# Simulation.net
KiCad netlist of a schematic drawn in Altium Designer
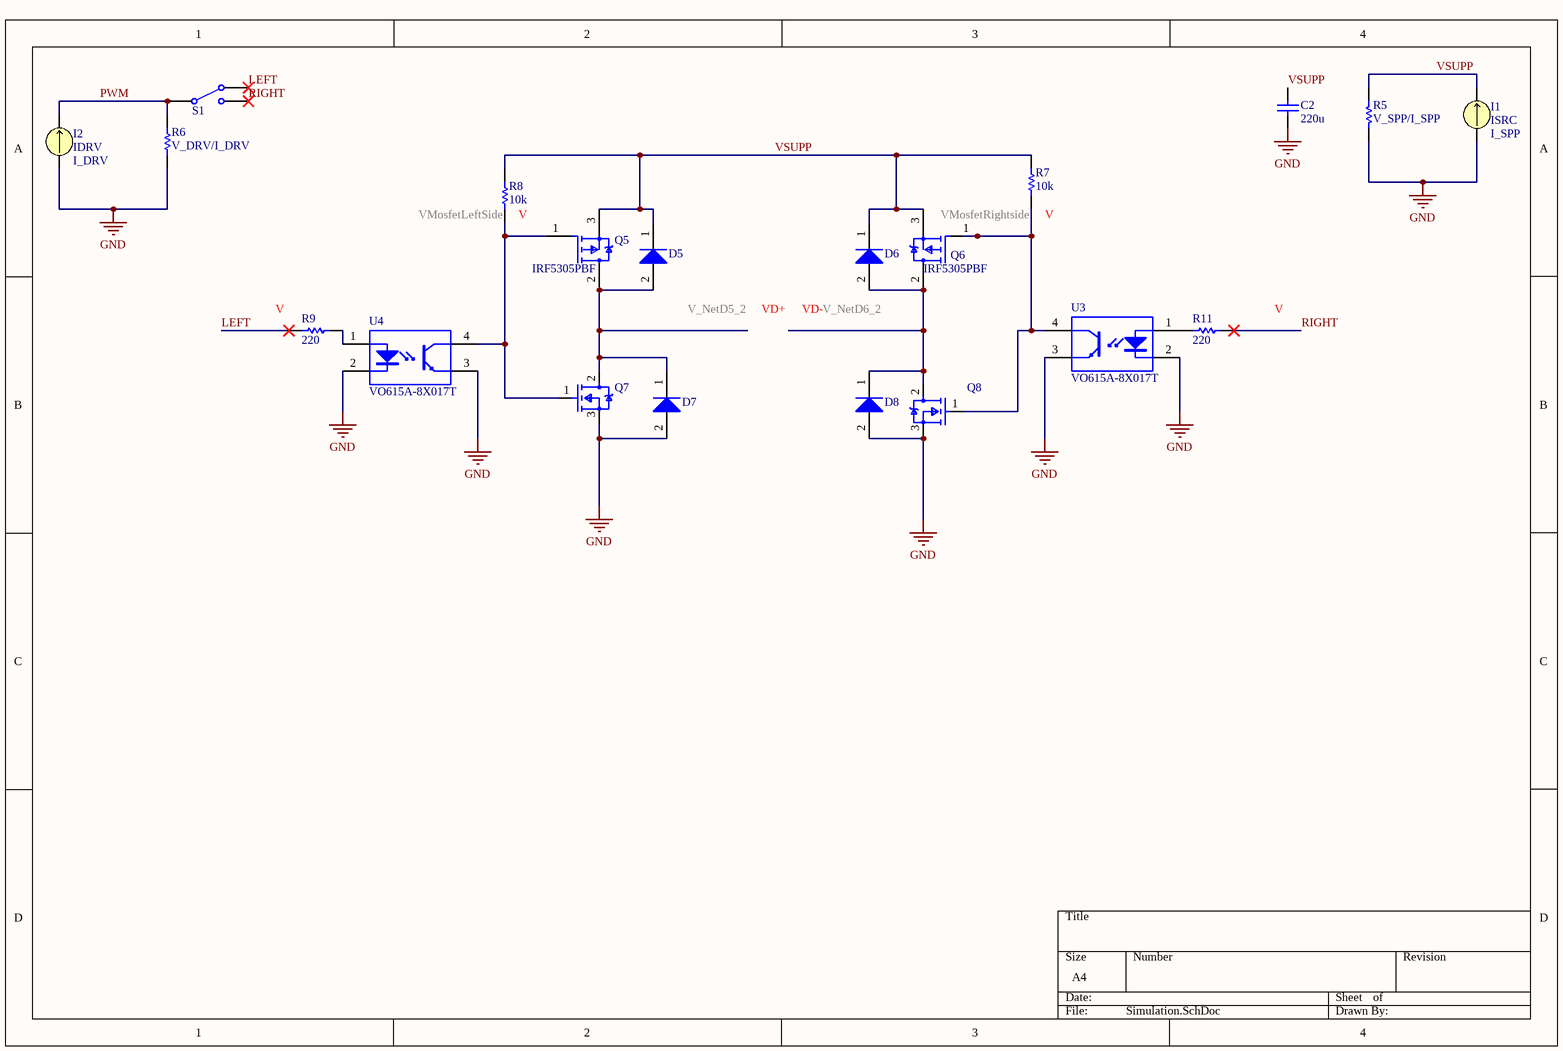
[diagram p0: Simulation.SchDoc]

(export (version "E")
  (design (tool "Eeschema 10.0.6"))
  (components
    (comp (ref "C2")
      (value "220u")
      (description "Capacitor")
      (libsource (lib "Simulation Generic Components") (part "Capacitor"))
    )
    (comp (ref "D5")
      (value "MUR410RLG")
      (footprint "ONSC-AXIAL_LEAD-2-267-05_V")
      (description "SWITCHMODE(TM) Power Rectifier, 2-Pin Axial_Lead, Pb-Free, Tape and Reel")
      (fields (field (name "MANUFACTURER") "On Semiconductor"))
      (libsource (lib "Altium Content Vault") (part "ONSC-D-K1A2-2"))
    )
    (comp (ref "D6")
      (value "MUR410RLG")
      (footprint "ONSC-AXIAL_LEAD-2-267-05_V")
      (description "SWITCHMODE(TM) Power Rectifier, 2-Pin Axial_Lead, Pb-Free, Tape and Reel")
      (fields (field (name "MANUFACTURER") "On Semiconductor"))
      (libsource (lib "Altium Content Vault") (part "ONSC-D-K1A2-2"))
    )
    (comp (ref "D7")
      (value "MUR410RLG")
      (footprint "ONSC-AXIAL_LEAD-2-267-05_V")
      (description "SWITCHMODE(TM) Power Rectifier, 2-Pin Axial_Lead, Pb-Free, Tape and Reel")
      (fields (field (name "MANUFACTURER") "On Semiconductor"))
      (libsource (lib "Altium Content Vault") (part "ONSC-D-K1A2-2"))
    )
    (comp (ref "D8")
      (value "MUR410RLG")
      (footprint "ONSC-AXIAL_LEAD-2-267-05_V")
      (description "SWITCHMODE(TM) Power Rectifier, 2-Pin Axial_Lead, Pb-Free, Tape and Reel")
      (fields (field (name "MANUFACTURER") "On Semiconductor"))
      (libsource (lib "Altium Content Vault") (part "ONSC-D-K1A2-2"))
    )
    (comp (ref "I1")
      (value "ISRC")
      (description "Current Source")
      (fields (field (name "ALTIUM_VALUE") "I_SPP") (field (name "PUBLISHER") "Altium Limited"))
      (libsource (lib "Simulation Generic Components") (part "ISRC"))
    )
    (comp (ref "I2")
      (value "IDRV")
      (description "Current Source")
      (fields (field (name "DC MAGNITUDE") "I_DRV") (field (name "PUBLISHER") "Altium Limited"))
      (libsource (lib "Simulation Generic Components") (part "ISRC"))
    )
    (comp (ref "Q5")
      (value "IRF5305PBF")
      (footprint "FP-PG-TO220-3-0")
      (description "MOSFET P-CH 55V 31A TO-220AB")
      (fields
        (field (name "OCTOPART") "https://octopart.com/irf5305pbf-infineon-65873396")
        (field (name "MANUFACTURER") "Infineon")
      )
      (libsource (lib "Altium Content Vault") (part "ef9d0aacdf366ab529cd174aea9d313"))
    )
    (comp (ref "Q6")
      (value "IRF5305PBF")
      (footprint "FP-PG-TO220-3-0")
      (description "MOSFET P-CH 55V 31A TO-220AB")
      (fields
        (field (name "OCTOPART") "https://octopart.com/irf5305pbf-infineon-65873396")
        (field (name "MANUFACTURER") "Infineon")
      )
      (libsource (lib "Altium Content Vault") (part "ef9d0aacdf366ab529cd174aea9d313"))
    )
    (comp (ref "Q7")
      (value "Trans_Infineon_IRF540NPBF_eec")
      (footprint "Infineon_IRF540NPBF_0")
      (description "TRANS MOSFET N-CH 100V 33A TO-220AB")
      (fields (field (name "PART NUMBER") "IRF540NPBF") (field (name "MANUFACTURER") "Infineon"))
      (libsource (lib "Trans_Infineon_IRF540NPBF_eec") (part "Trans_Infineon_IRF540NPBF_eec"))
    )
    (comp (ref "Q8")
      (value "Trans_Infineon_IRF540NPBF_eec")
      (footprint "Infineon_IRF540NPBF_0")
      (description "TRANS MOSFET N-CH 100V 33A TO-220AB")
      (fields (field (name "PART NUMBER") "IRF540NPBF") (field (name "MANUFACTURER") "Infineon"))
      (libsource (lib "Trans_Infineon_IRF540NPBF_eec") (part "Trans_Infineon_IRF540NPBF_eec"))
    )
    (comp (ref "R5")
      (value "V_SPP/I_SPP")
      (description "Resistor")
      (libsource (lib "Simulation Generic Components") (part "Resistor"))
    )
    (comp (ref "R6")
      (value "V_DRV/I_DRV")
      (description "Resistor")
      (libsource (lib "Simulation Generic Components") (part "Resistor"))
    )
    (comp (ref "R7")
      (value "10k")
      (description "Resistor")
      (libsource (lib "Simulation Generic Components") (part "Resistor"))
    )
    (comp (ref "R8")
      (value "10k")
      (description "Resistor")
      (libsource (lib "Simulation Generic Components") (part "Resistor"))
    )
    (comp (ref "R9")
      (value "220")
      (description "Resistor")
      (libsource (lib "Simulation Generic Components") (part "Resistor"))
    )
    (comp (ref "R11")
      (value "220")
      (description "Resistor")
      (libsource (lib "Simulation Generic Components") (part "Resistor"))
    )
    (comp (ref "S1")
      (value "Single-Pole, Double-Throw Switch")
      (libsource (lib "Simulation Generic Components") (part "SPDT SW"))
    )
    (comp (ref "U3")
      (value "VO615A-8X017T")
      (footprint "VISH-VO615A-XX017T_V")
      (fields (field (name "MANUFACTURER") "Vishay"))
      (libsource (lib "Altium Content Vault") (part "OPTO-AKEC-4"))
    )
    (comp (ref "U4")
      (value "VO615A-8X017T")
      (footprint "VISH-VO615A-XX017T_V")
      (fields (field (name "MANUFACTURER") "Vishay"))
      (libsource (lib "Altium Content Vault") (part "OPTO-AKEC-4"))
    )
  )
  (nets
    (net (code "2") (name "/LEFT") (class "Default")
      (node (ref "R9") (pin "2") (pinfunction "2_2") (pintype "passive"))
      (node (ref "S1") (pin "3") (pinfunction "3_3") (pintype "passive"))
    )
    (net (code "3") (name "/PWM") (class "Default")
      (node (ref "I2") (pin "2") (pinfunction "2_2") (pintype "passive"))
      (node (ref "R6") (pin "2") (pinfunction "2_2") (pintype "passive"))
      (node (ref "S1") (pin "1") (pinfunction "1_1") (pintype "passive"))
    )
    (net (code "4") (name "/RIGHT") (class "Default")
      (node (ref "R11") (pin "1") (pinfunction "1_1") (pintype "passive"))
      (node (ref "S1") (pin "2") (pinfunction "2_2") (pintype "passive"))
    )
    (net (code "5") (name "/VSUPP") (class "Default")
      (node (ref "C2") (pin "1") (pinfunction "1_1") (pintype "passive"))
      (node (ref "D5") (pin "1") (pinfunction "K_1") (pintype "passive"))
      (node (ref "D6") (pin "1") (pinfunction "K_1") (pintype "passive"))
      (node (ref "I1") (pin "2") (pinfunction "2_2") (pintype "passive"))
      (node (ref "Q5") (pin "3") (pinfunction "S_3") (pintype "passive"))
      (node (ref "Q6") (pin "3") (pinfunction "S_3") (pintype "passive"))
      (node (ref "R5") (pin "2") (pinfunction "2_2") (pintype "passive"))
      (node (ref "R7") (pin "2") (pinfunction "2_2") (pintype "passive"))
      (node (ref "R8") (pin "2") (pinfunction "2_2") (pintype "passive"))
    )
    (net (code "6") (name "GND") (class "Default")
      (node (ref "C2") (pin "2") (pinfunction "2_2") (pintype "passive"))
      (node (ref "D7") (pin "2") (pinfunction "A_2") (pintype "passive"))
      (node (ref "D8") (pin "2") (pinfunction "A_2") (pintype "passive"))
      (node (ref "I1") (pin "1") (pinfunction "1_1") (pintype "passive"))
      (node (ref "I2") (pin "1") (pinfunction "1_1") (pintype "passive"))
      (node (ref "Q7") (pin "3") (pinfunction "SOURCE_3") (pintype "passive"))
      (node (ref "Q8") (pin "3") (pinfunction "SOURCE_3") (pintype "passive"))
      (node (ref "R5") (pin "1") (pinfunction "1_1") (pintype "passive"))
      (node (ref "R6") (pin "1") (pinfunction "1_1") (pintype "passive"))
      (node (ref "U3") (pin "2") (pinfunction "CATHODE_2") (pintype "passive"))
      (node (ref "U3") (pin "3") (pinfunction "EMITTER_3") (pintype "passive"))
      (node (ref "U4") (pin "2") (pinfunction "CATHODE_2") (pintype "passive"))
      (node (ref "U4") (pin "3") (pinfunction "EMITTER_3") (pintype "passive"))
    )
    (net (code "7") (name "Net-(D5-A)") (class "Default")
      (node (ref "D5") (pin "2") (pinfunction "A_2") (pintype "passive"))
      (node (ref "D7") (pin "1") (pinfunction "K_1") (pintype "passive"))
      (node (ref "Q5") (pin "2") (pinfunction "D_2") (pintype "passive"))
      (node (ref "Q7") (pin "2") (pinfunction "DRAIN_2") (pintype "passive"))
    )
    (net (code "8") (name "Net-(D6-A)") (class "Default")
      (node (ref "D6") (pin "2") (pinfunction "A_2") (pintype "passive"))
      (node (ref "D8") (pin "1") (pinfunction "K_1") (pintype "passive"))
      (node (ref "Q6") (pin "2") (pinfunction "D_2") (pintype "passive"))
      (node (ref "Q8") (pin "2") (pinfunction "DRAIN_2") (pintype "passive"))
    )
    (net (code "9") (name "Net-(Q5-G)") (class "Default")
      (node (ref "Q5") (pin "1") (pinfunction "G_1") (pintype "passive"))
      (node (ref "Q7") (pin "1") (pinfunction "GATE_1") (pintype "passive"))
      (node (ref "R8") (pin "1") (pinfunction "1_1") (pintype "passive"))
      (node (ref "U4") (pin "4") (pinfunction "COLLECTOR_4") (pintype "passive"))
    )
    (net (code "10") (name "Net-(Q6-G)") (class "Default")
      (node (ref "Q6") (pin "1") (pinfunction "G_1") (pintype "passive"))
      (node (ref "Q8") (pin "1") (pinfunction "GATE_1") (pintype "passive"))
      (node (ref "R7") (pin "1") (pinfunction "1_1") (pintype "passive"))
      (node (ref "U3") (pin "4") (pinfunction "COLLECTOR_4") (pintype "passive"))
    )
    (net (code "11") (name "Net-(U3-ANODE)") (class "Default")
      (node (ref "R11") (pin "2") (pinfunction "2_2") (pintype "passive"))
      (node (ref "U3") (pin "1") (pinfunction "ANODE_1") (pintype "passive"))
    )
    (net (code "12") (name "Net-(U4-ANODE)") (class "Default")
      (node (ref "R9") (pin "1") (pinfunction "1_1") (pintype "passive"))
      (node (ref "U4") (pin "1") (pinfunction "ANODE_1") (pintype "passive"))
    )
  )
)
